# tempature.net
KiCad netlist of a schematic drawn in Altium Designer
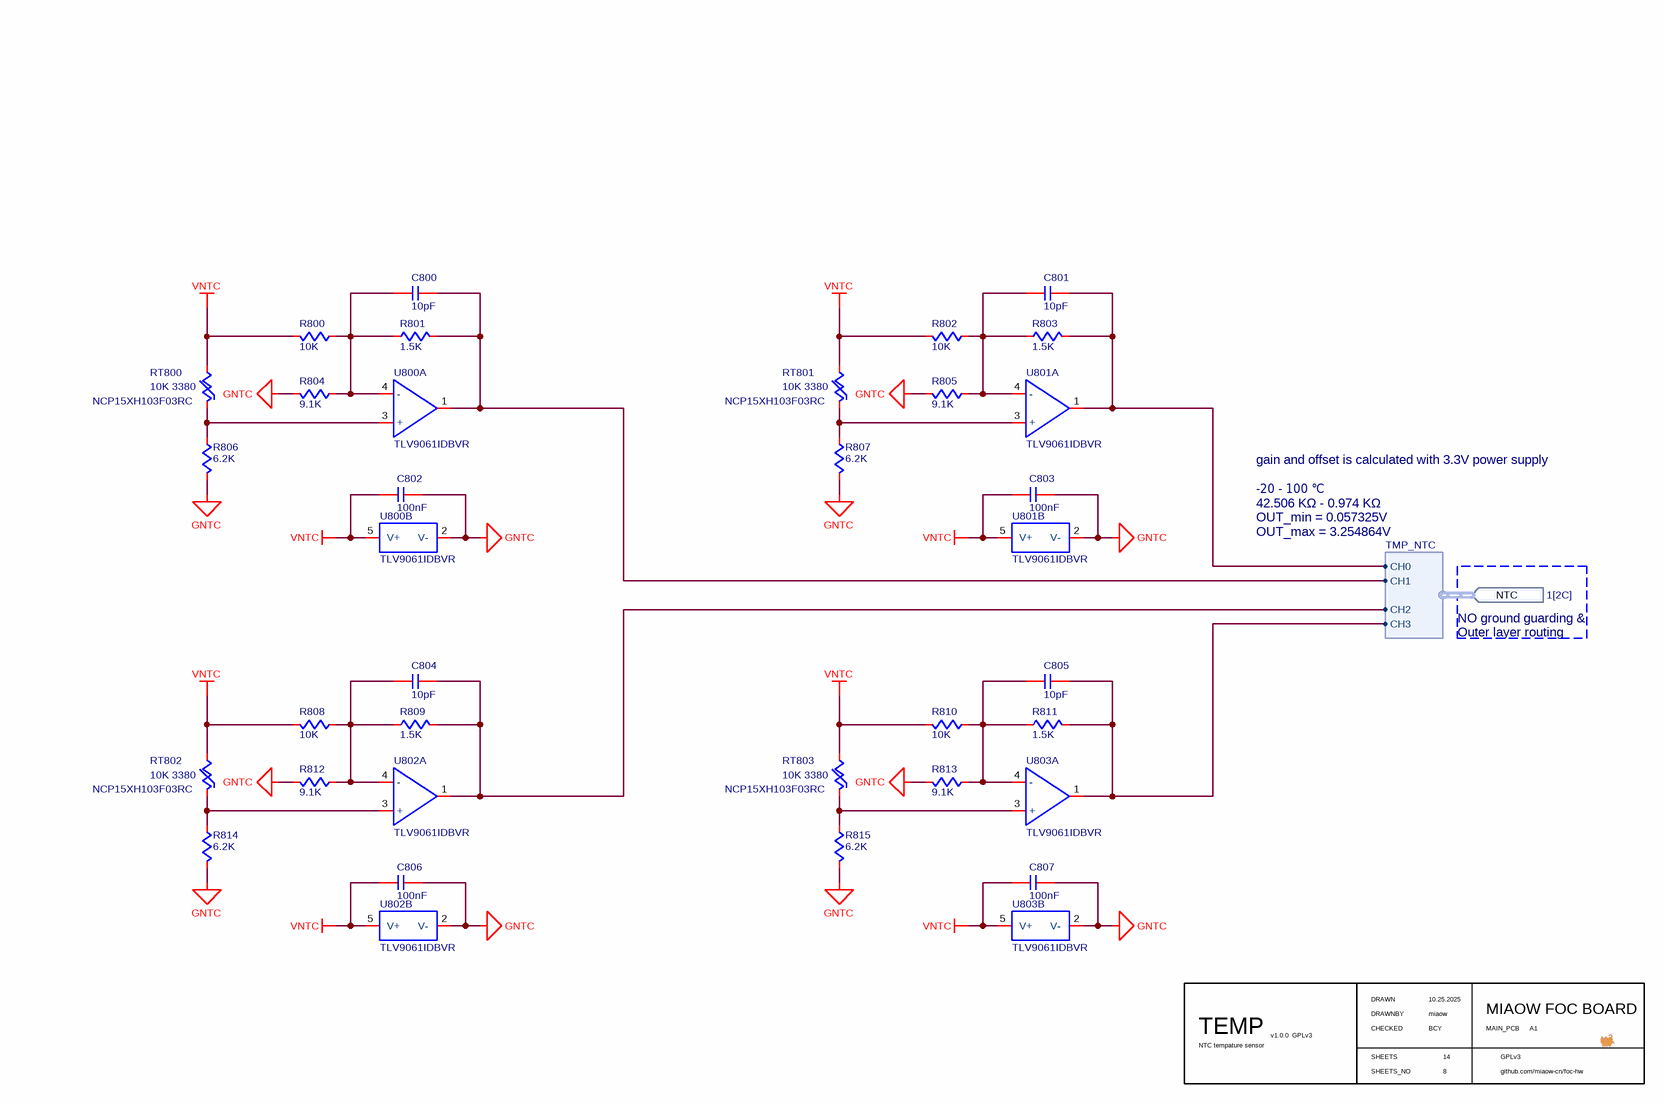
[diagram p0: tempature.schdoc]

(export (version "E")
  (design (tool "Eeschema 10.0.6"))
  (components
    (comp (ref "C800")
      (value "10pF")
      (footprint "mw:C0402")
      (fields (field (name "VOLTAGE") "25V") (field (name "Comment") "C-NOMO"))
      (libsource (lib "mw") (part "C-NOMO"))
    )
    (comp (ref "C801")
      (value "10pF")
      (footprint "mw:C0402")
      (fields (field (name "VOLTAGE") "25V") (field (name "Comment") "C-NOMO"))
      (libsource (lib "mw") (part "C-NOMO"))
    )
    (comp (ref "C802")
      (value "100nF")
      (footprint "mw:C0402")
      (fields (field (name "VOLTAGE") "25V") (field (name "Comment") "C-NOMO"))
      (libsource (lib "mw") (part "C-NOMO"))
    )
    (comp (ref "C803")
      (value "100nF")
      (footprint "mw:C0402")
      (fields (field (name "VOLTAGE") "25V") (field (name "Comment") "C-NOMO"))
      (libsource (lib "mw") (part "C-NOMO"))
    )
    (comp (ref "C804")
      (value "10pF")
      (footprint "mw:C0402")
      (fields (field (name "VOLTAGE") "25V") (field (name "Comment") "C-NOMO"))
      (libsource (lib "mw") (part "C-NOMO"))
    )
    (comp (ref "C805")
      (value "10pF")
      (footprint "mw:C0402")
      (fields (field (name "VOLTAGE") "25V") (field (name "Comment") "C-NOMO"))
      (libsource (lib "mw") (part "C-NOMO"))
    )
    (comp (ref "C806")
      (value "100nF")
      (footprint "mw:C0402")
      (fields (field (name "VOLTAGE") "25V") (field (name "Comment") "C-NOMO"))
      (libsource (lib "mw") (part "C-NOMO"))
    )
    (comp (ref "C807")
      (value "100nF")
      (footprint "mw:C0402")
      (fields (field (name "VOLTAGE") "25V") (field (name "Comment") "C-NOMO"))
      (libsource (lib "mw") (part "C-NOMO"))
    )
    (comp (ref "R800")
      (value "10K")
      (footprint "mw:R0402")
      (fields (field (name "Comment") "R"))
      (libsource (lib "mw") (part "R"))
    )
    (comp (ref "R801")
      (value "1.5K")
      (footprint "mw:R0402")
      (fields (field (name "Comment") "R"))
      (libsource (lib "mw") (part "R"))
    )
    (comp (ref "R802")
      (value "10K")
      (footprint "mw:R0402")
      (fields (field (name "Comment") "R"))
      (libsource (lib "mw") (part "R"))
    )
    (comp (ref "R803")
      (value "1.5K")
      (footprint "mw:R0402")
      (fields (field (name "Comment") "R"))
      (libsource (lib "mw") (part "R"))
    )
    (comp (ref "R804")
      (value "9.1K")
      (footprint "mw:R0402")
      (fields (field (name "Comment") "R"))
      (libsource (lib "mw") (part "R"))
    )
    (comp (ref "R805")
      (value "9.1K")
      (footprint "mw:R0402")
      (fields (field (name "Comment") "R"))
      (libsource (lib "mw") (part "R"))
    )
    (comp (ref "R806")
      (value "6.2K")
      (footprint "mw:R0402")
      (fields (field (name "Comment") "R"))
      (libsource (lib "mw") (part "R"))
    )
    (comp (ref "R807")
      (value "6.2K")
      (footprint "mw:R0402")
      (fields (field (name "Comment") "R"))
      (libsource (lib "mw") (part "R"))
    )
    (comp (ref "R808")
      (value "10K")
      (footprint "mw:R0402")
      (fields (field (name "Comment") "R"))
      (libsource (lib "mw") (part "R"))
    )
    (comp (ref "R809")
      (value "1.5K")
      (footprint "mw:R0402")
      (fields (field (name "Comment") "R"))
      (libsource (lib "mw") (part "R"))
    )
    (comp (ref "R810")
      (value "10K")
      (footprint "mw:R0402")
      (fields (field (name "Comment") "R"))
      (libsource (lib "mw") (part "R"))
    )
    (comp (ref "R811")
      (value "1.5K")
      (footprint "mw:R0402")
      (fields (field (name "Comment") "R"))
      (libsource (lib "mw") (part "R"))
    )
    (comp (ref "R812")
      (value "9.1K")
      (footprint "mw:R0402")
      (fields (field (name "Comment") "R"))
      (libsource (lib "mw") (part "R"))
    )
    (comp (ref "R813")
      (value "9.1K")
      (footprint "mw:R0402")
      (fields (field (name "Comment") "R"))
      (libsource (lib "mw") (part "R"))
    )
    (comp (ref "R814")
      (value "6.2K")
      (footprint "mw:R0402")
      (fields (field (name "Comment") "R"))
      (libsource (lib "mw") (part "R"))
    )
    (comp (ref "R815")
      (value "6.2K")
      (footprint "mw:R0402")
      (fields (field (name "Comment") "R"))
      (libsource (lib "mw") (part "R"))
    )
    (comp (ref "RT800")
      (value "NCP15XH103F03RC")
      (footprint "mw:NTC0402")
      (description "NTC - 10K, 3380, 1%")
      (fields (field (name "ALTIUM_VALUE") "10K 3380"))
      (libsource (lib "mw") (part "NCP15XH103F03RC"))
    )
    (comp (ref "RT801")
      (value "NCP15XH103F03RC")
      (footprint "mw:NTC0402")
      (description "NTC - 10K, 3380, 1%")
      (fields (field (name "ALTIUM_VALUE") "10K 3380"))
      (libsource (lib "mw") (part "NCP15XH103F03RC"))
    )
    (comp (ref "RT802")
      (value "NCP15XH103F03RC")
      (footprint "mw:NTC0402")
      (description "NTC - 10K, 3380, 1%")
      (fields (field (name "ALTIUM_VALUE") "10K 3380"))
      (libsource (lib "mw") (part "NCP15XH103F03RC"))
    )
    (comp (ref "RT803")
      (value "NCP15XH103F03RC")
      (footprint "mw:NTC0402")
      (description "NTC - 10K, 3380, 1%")
      (fields (field (name "ALTIUM_VALUE") "10K 3380"))
      (libsource (lib "mw") (part "NCP15XH103F03RC"))
    )
    (comp (ref "U800")
      (value "TLV9061IDBVR")
      (footprint "mw:TLV9061IDBVR")
      (description "OPA - 1ch, 1.8V - 5.5V, r2r, 0.3mV, 10MHz, 10nVHz^0.5, 0.5pA")
      (libsource (lib "mw") (part "TLV9061IDBVR"))
    )
    (comp (ref "U801")
      (value "TLV9061IDBVR")
      (footprint "mw:TLV9061IDBVR")
      (description "OPA - 1ch, 1.8V - 5.5V, r2r, 0.3mV, 10MHz, 10nVHz^0.5, 0.5pA")
      (libsource (lib "mw") (part "TLV9061IDBVR"))
    )
    (comp (ref "U802")
      (value "TLV9061IDBVR")
      (footprint "mw:TLV9061IDBVR")
      (description "OPA - 1ch, 1.8V - 5.5V, r2r, 0.3mV, 10MHz, 10nVHz^0.5, 0.5pA")
      (libsource (lib "mw") (part "TLV9061IDBVR"))
    )
    (comp (ref "U803")
      (value "TLV9061IDBVR")
      (footprint "mw:TLV9061IDBVR")
      (description "OPA - 1ch, 1.8V - 5.5V, r2r, 0.3mV, 10MHz, 10nVHz^0.5, 0.5pA")
      (libsource (lib "mw") (part "TLV9061IDBVR"))
    )
  )
  (nets
    (net (code "3") (name "GNTC") (class "Default")
      (node (ref "C802") (pin "1") (pinfunction "1_1") (pintype "passive"))
      (node (ref "C803") (pin "1") (pinfunction "1_1") (pintype "passive"))
      (node (ref "C806") (pin "1") (pinfunction "1_1") (pintype "passive"))
      (node (ref "C807") (pin "1") (pinfunction "1_1") (pintype "passive"))
      (node (ref "R804") (pin "1") (pinfunction "1_1") (pintype "passive"))
      (node (ref "R805") (pin "1") (pinfunction "1_1") (pintype "passive"))
      (node (ref "R806") (pin "1") (pinfunction "1_1") (pintype "passive"))
      (node (ref "R807") (pin "1") (pinfunction "1_1") (pintype "passive"))
      (node (ref "R812") (pin "1") (pinfunction "1_1") (pintype "passive"))
      (node (ref "R813") (pin "1") (pinfunction "1_1") (pintype "passive"))
      (node (ref "R814") (pin "1") (pinfunction "1_1") (pintype "passive"))
      (node (ref "R815") (pin "1") (pinfunction "1_1") (pintype "passive"))
      (node (ref "U800") (pin "2") (pinfunction "V-_2") (pintype "passive"))
      (node (ref "U801") (pin "2") (pinfunction "V-_2") (pintype "passive"))
      (node (ref "U802") (pin "2") (pinfunction "V-_2") (pintype "passive"))
      (node (ref "U803") (pin "2") (pinfunction "V-_2") (pintype "passive"))
    )
    (net (code "4") (name "Net-(U800A-+)") (class "Default")
      (node (ref "R806") (pin "2") (pinfunction "2_2") (pintype "passive"))
      (node (ref "RT800") (pin "1") (pinfunction "1_1") (pintype "passive"))
      (node (ref "U800") (pin "3") (pinfunction "+_3") (pintype "passive"))
    )
    (net (code "5") (name "Net-(U800A--)") (class "Default")
      (node (ref "C800") (pin "2") (pinfunction "2_2") (pintype "passive"))
      (node (ref "R800") (pin "2") (pinfunction "2_2") (pintype "passive"))
      (node (ref "R801") (pin "2") (pinfunction "2_2") (pintype "passive"))
      (node (ref "R804") (pin "2") (pinfunction "2_2") (pintype "passive"))
      (node (ref "U800") (pin "4") (pinfunction "-_4") (pintype "passive"))
    )
    (net (code "6") (name "Net-(U800A-OUT)") (class "Default")
      (node (ref "C800") (pin "1") (pinfunction "1_1") (pintype "passive"))
      (node (ref "R801") (pin "1") (pinfunction "1_1") (pintype "passive"))
      (node (ref "U800") (pin "1") (pinfunction "OUT_1") (pintype "passive"))
    )
    (net (code "7") (name "Net-(U801A-+)") (class "Default")
      (node (ref "R807") (pin "2") (pinfunction "2_2") (pintype "passive"))
      (node (ref "RT801") (pin "1") (pinfunction "1_1") (pintype "passive"))
      (node (ref "U801") (pin "3") (pinfunction "+_3") (pintype "passive"))
    )
    (net (code "8") (name "Net-(U801A--)") (class "Default")
      (node (ref "C801") (pin "2") (pinfunction "2_2") (pintype "passive"))
      (node (ref "R802") (pin "2") (pinfunction "2_2") (pintype "passive"))
      (node (ref "R803") (pin "2") (pinfunction "2_2") (pintype "passive"))
      (node (ref "R805") (pin "2") (pinfunction "2_2") (pintype "passive"))
      (node (ref "U801") (pin "4") (pinfunction "-_4") (pintype "passive"))
    )
    (net (code "9") (name "Net-(U801A-OUT)") (class "Default")
      (node (ref "C801") (pin "1") (pinfunction "1_1") (pintype "passive"))
      (node (ref "R803") (pin "1") (pinfunction "1_1") (pintype "passive"))
      (node (ref "U801") (pin "1") (pinfunction "OUT_1") (pintype "passive"))
    )
    (net (code "10") (name "Net-(U802A-+)") (class "Default")
      (node (ref "R814") (pin "2") (pinfunction "2_2") (pintype "passive"))
      (node (ref "RT802") (pin "1") (pinfunction "1_1") (pintype "passive"))
      (node (ref "U802") (pin "3") (pinfunction "+_3") (pintype "passive"))
    )
    (net (code "11") (name "Net-(U802A--)") (class "Default")
      (node (ref "C804") (pin "2") (pinfunction "2_2") (pintype "passive"))
      (node (ref "R808") (pin "2") (pinfunction "2_2") (pintype "passive"))
      (node (ref "R809") (pin "2") (pinfunction "2_2") (pintype "passive"))
      (node (ref "R812") (pin "2") (pinfunction "2_2") (pintype "passive"))
      (node (ref "U802") (pin "4") (pinfunction "-_4") (pintype "passive"))
    )
    (net (code "12") (name "Net-(U802A-OUT)") (class "Default")
      (node (ref "C804") (pin "1") (pinfunction "1_1") (pintype "passive"))
      (node (ref "R809") (pin "1") (pinfunction "1_1") (pintype "passive"))
      (node (ref "U802") (pin "1") (pinfunction "OUT_1") (pintype "passive"))
    )
    (net (code "13") (name "Net-(U803A-+)") (class "Default")
      (node (ref "R815") (pin "2") (pinfunction "2_2") (pintype "passive"))
      (node (ref "RT803") (pin "1") (pinfunction "1_1") (pintype "passive"))
      (node (ref "U803") (pin "3") (pinfunction "+_3") (pintype "passive"))
    )
    (net (code "14") (name "Net-(U803A--)") (class "Default")
      (node (ref "C805") (pin "2") (pinfunction "2_2") (pintype "passive"))
      (node (ref "R810") (pin "2") (pinfunction "2_2") (pintype "passive"))
      (node (ref "R811") (pin "2") (pinfunction "2_2") (pintype "passive"))
      (node (ref "R813") (pin "2") (pinfunction "2_2") (pintype "passive"))
      (node (ref "U803") (pin "4") (pinfunction "-_4") (pintype "passive"))
    )
    (net (code "15") (name "Net-(U803A-OUT)") (class "Default")
      (node (ref "C805") (pin "1") (pinfunction "1_1") (pintype "passive"))
      (node (ref "R811") (pin "1") (pinfunction "1_1") (pintype "passive"))
      (node (ref "U803") (pin "1") (pinfunction "OUT_1") (pintype "passive"))
    )
    (net (code "16") (name "VNTC") (class "Default")
      (node (ref "C802") (pin "2") (pinfunction "2_2") (pintype "passive"))
      (node (ref "C803") (pin "2") (pinfunction "2_2") (pintype "passive"))
      (node (ref "C806") (pin "2") (pinfunction "2_2") (pintype "passive"))
      (node (ref "C807") (pin "2") (pinfunction "2_2") (pintype "passive"))
      (node (ref "R800") (pin "1") (pinfunction "1_1") (pintype "passive"))
      (node (ref "R802") (pin "1") (pinfunction "1_1") (pintype "passive"))
      (node (ref "R808") (pin "1") (pinfunction "1_1") (pintype "passive"))
      (node (ref "R810") (pin "1") (pinfunction "1_1") (pintype "passive"))
      (node (ref "RT800") (pin "2") (pinfunction "2_2") (pintype "passive"))
      (node (ref "RT801") (pin "2") (pinfunction "2_2") (pintype "passive"))
      (node (ref "RT802") (pin "2") (pinfunction "2_2") (pintype "passive"))
      (node (ref "RT803") (pin "2") (pinfunction "2_2") (pintype "passive"))
      (node (ref "U800") (pin "5") (pinfunction "V+_5") (pintype "passive"))
      (node (ref "U801") (pin "5") (pinfunction "V+_5") (pintype "passive"))
      (node (ref "U802") (pin "5") (pinfunction "V+_5") (pintype "passive"))
      (node (ref "U803") (pin "5") (pinfunction "V+_5") (pintype "passive"))
    )
  )
)
